# 4_MotorDrive.net
KiCad netlist of a schematic drawn in Altium Designer
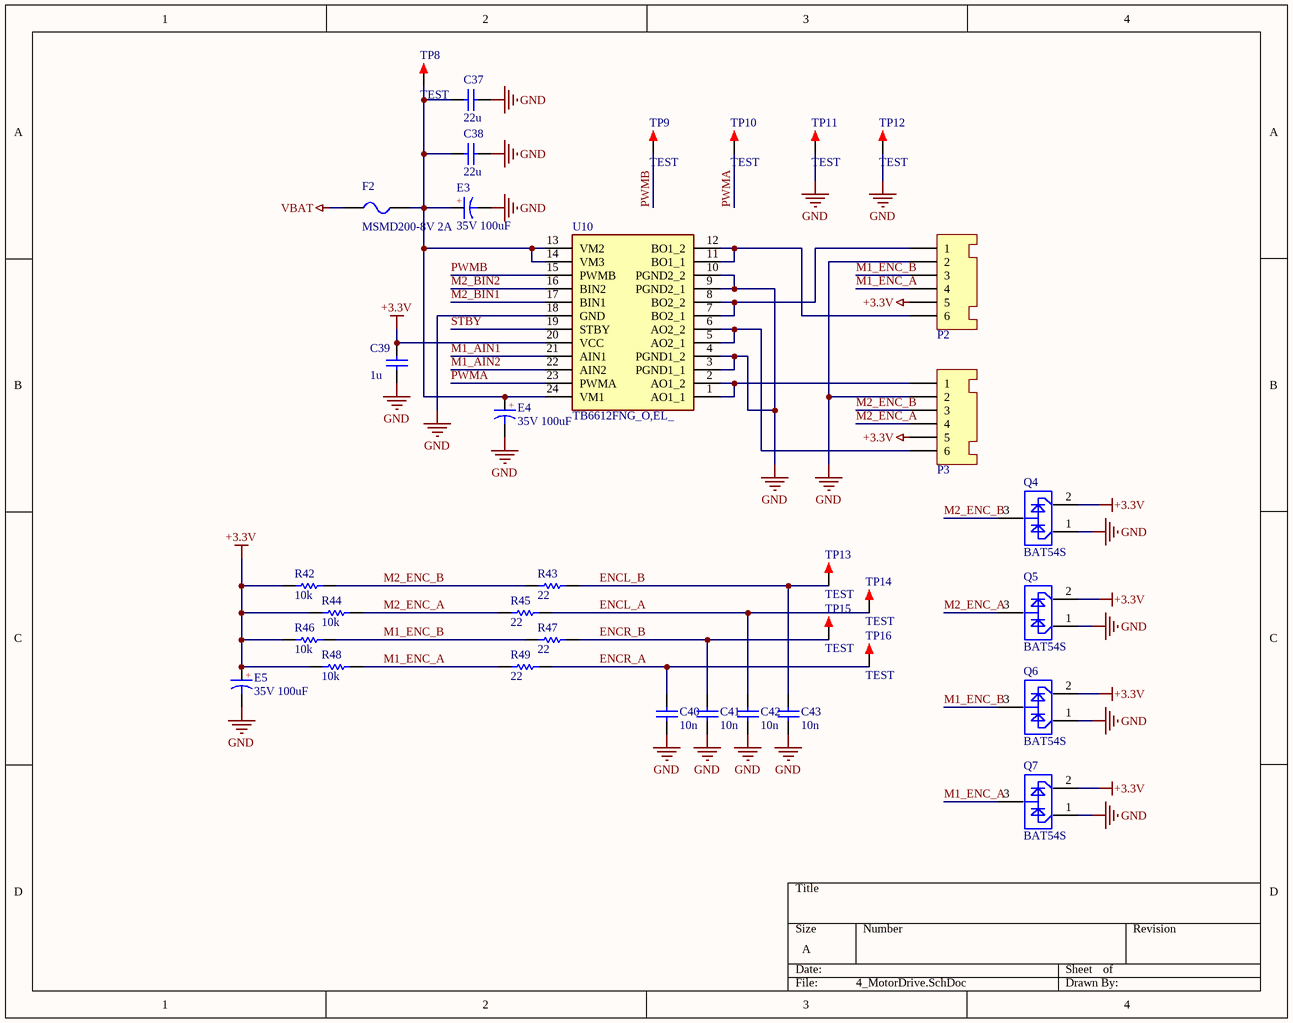
[diagram p0: 4_MotorDrive.SchDoc]

(export (version "E")
  (design (tool "Eeschema 10.0.6"))
  (components
    (comp (ref "C37")
      (value "22u")
      (footprint "C1812_L")
      (description "贴片电容")
      (libsource (lib "0.1 - 电阻-电容-电感-电位器") (part "C"))
    )
    (comp (ref "C38")
      (value "22u")
      (footprint "C1812_L")
      (description "贴片电容")
      (libsource (lib "0.1 - 电阻-电容-电感-电位器") (part "C"))
    )
    (comp (ref "C39")
      (value "1u")
      (footprint "CAP_0603_SMD")
      (description "Capacitor, 0603, SMD")
      (fields (field (name "PUBLISHER") "Altium Limited"))
      (libsource (lib "myRLC") (part "CAP_0603_SMD"))
    )
    (comp (ref "C40")
      (value "10n")
      (footprint "CAP_0603_SMD")
      (description "Capacitor, 0603, SMD")
      (fields (field (name "PUBLISHER") "Altium Limited"))
      (libsource (lib "myRLC") (part "CAP_0603_SMD"))
    )
    (comp (ref "C41")
      (value "10n")
      (footprint "CAP_0603_SMD")
      (description "Capacitor, 0603, SMD")
      (fields (field (name "PUBLISHER") "Altium Limited"))
      (libsource (lib "myRLC") (part "CAP_0603_SMD"))
    )
    (comp (ref "C42")
      (value "10n")
      (footprint "CAP_0603_SMD")
      (description "Capacitor, 0603, SMD")
      (fields (field (name "PUBLISHER") "Altium Limited"))
      (libsource (lib "myRLC") (part "CAP_0603_SMD"))
    )
    (comp (ref "C43")
      (value "10n")
      (footprint "CAP_0603_SMD")
      (description "Capacitor, 0603, SMD")
      (fields (field (name "PUBLISHER") "Altium Limited"))
      (libsource (lib "myRLC") (part "CAP_0603_SMD"))
    )
    (comp (ref "E3")
      (value "35V 100uF")
      (footprint "CE D(6.3*7.7)")
      (description "贴片电解电容")
      (libsource (lib "0.1 - 电阻-电容-电感-电位器") (part "CE_SMD"))
    )
    (comp (ref "E4")
      (value "35V 100uF")
      (footprint "CE D(6.3*7.7)")
      (description "贴片电解电容")
      (libsource (lib "0.1 - 电阻-电容-电感-电位器") (part "CE_SMD"))
    )
    (comp (ref "E5")
      (value "35V 100uF")
      (footprint "CE D(6.3*7.7)")
      (description "贴片电解电容")
      (libsource (lib "0.1 - 电阻-电容-电感-电位器") (part "CE_SMD"))
    )
    (comp (ref "F2")
      (value "MSMD200-8V 2A")
      (footprint "FU 1812")
      (description "贴片保险丝")
      (libsource (lib "0.5 - 保险丝-晶振-光耦") (part "FU"))
    )
    (comp (ref "P2")
      (value "HDR-1X6")
      (footprint "XH2.54-WS-6P")
      (description "6P接插件")
      (libsource (lib "5.4 - 接插件-脚距2.54 (100mil) ") (part "Header 6"))
    )
    (comp (ref "P3")
      (value "HDR-1X6")
      (footprint "XH2.54-WS-6P")
      (description "6P接插件")
      (libsource (lib "5.4 - 接插件-脚距2.54 (100mil) ") (part "Header 6"))
    )
    (comp (ref "Q4")
      (value "BAT54S")
      (footprint "TR_SOT-23")
      (description "Dual Schottky Diodes, SOT23")
      (libsource (lib "myTransistors&Diodes") (part "BAT54S"))
    )
    (comp (ref "Q5")
      (value "BAT54S")
      (footprint "TR_SOT-23")
      (description "Dual Schottky Diodes, SOT23")
      (libsource (lib "myTransistors&Diodes") (part "BAT54S"))
    )
    (comp (ref "Q6")
      (value "BAT54S")
      (footprint "TR_SOT-23")
      (description "Dual Schottky Diodes, SOT23")
      (libsource (lib "myTransistors&Diodes") (part "BAT54S"))
    )
    (comp (ref "Q7")
      (value "BAT54S")
      (footprint "TR_SOT-23")
      (description "Dual Schottky Diodes, SOT23")
      (libsource (lib "myTransistors&Diodes") (part "BAT54S"))
    )
    (comp (ref "R42")
      (value "10k")
      (footprint "RES_0603_SMD")
      (description "Resistor, 0603, SMD")
      (fields (field (name "PUBLISHER") "Altium Limited"))
      (libsource (lib "myRLC") (part "RES_0603_SMD"))
    )
    (comp (ref "R43")
      (value "22")
      (footprint "RES_0603_SMD")
      (description "Resistor, 0603, SMD")
      (fields (field (name "PUBLISHER") "Altium Limited"))
      (libsource (lib "myRLC") (part "RES_0603_SMD"))
    )
    (comp (ref "R44")
      (value "10k")
      (footprint "RES_0603_SMD")
      (description "Resistor, 0603, SMD")
      (fields (field (name "PUBLISHER") "Altium Limited"))
      (libsource (lib "myRLC") (part "RES_0603_SMD"))
    )
    (comp (ref "R45")
      (value "22")
      (footprint "RES_0603_SMD")
      (description "Resistor, 0603, SMD")
      (fields (field (name "PUBLISHER") "Altium Limited"))
      (libsource (lib "myRLC") (part "RES_0603_SMD"))
    )
    (comp (ref "R46")
      (value "10k")
      (footprint "RES_0603_SMD")
      (description "Resistor, 0603, SMD")
      (fields (field (name "PUBLISHER") "Altium Limited"))
      (libsource (lib "myRLC") (part "RES_0603_SMD"))
    )
    (comp (ref "R47")
      (value "22")
      (footprint "RES_0603_SMD")
      (description "Resistor, 0603, SMD")
      (fields (field (name "PUBLISHER") "Altium Limited"))
      (libsource (lib "myRLC") (part "RES_0603_SMD"))
    )
    (comp (ref "R48")
      (value "10k")
      (footprint "RES_0603_SMD")
      (description "Resistor, 0603, SMD")
      (fields (field (name "PUBLISHER") "Altium Limited"))
      (libsource (lib "myRLC") (part "RES_0603_SMD"))
    )
    (comp (ref "R49")
      (value "22")
      (footprint "RES_0603_SMD")
      (description "Resistor, 0603, SMD")
      (fields (field (name "PUBLISHER") "Altium Limited"))
      (libsource (lib "myRLC") (part "RES_0603_SMD"))
    )
    (comp (ref "TP8")
      (value "TEST")
      (footprint "TEST 1.2")
      (description "测试点")
      (libsource (lib "0.7 - 常用按键-开关-蜂鸣器-电池-测试点") (part "TEST"))
    )
    (comp (ref "TP9")
      (value "TEST")
      (footprint "TEST 1.2")
      (description "测试点")
      (libsource (lib "0.7 - 常用按键-开关-蜂鸣器-电池-测试点") (part "TEST"))
    )
    (comp (ref "TP10")
      (value "TEST")
      (footprint "TEST 1.2")
      (description "测试点")
      (libsource (lib "0.7 - 常用按键-开关-蜂鸣器-电池-测试点") (part "TEST"))
    )
    (comp (ref "TP11")
      (value "TEST")
      (footprint "TEST 1.2")
      (description "测试点")
      (libsource (lib "0.7 - 常用按键-开关-蜂鸣器-电池-测试点") (part "TEST"))
    )
    (comp (ref "TP12")
      (value "TEST")
      (footprint "TEST 1.2")
      (description "测试点")
      (libsource (lib "0.7 - 常用按键-开关-蜂鸣器-电池-测试点") (part "TEST"))
    )
    (comp (ref "TP13")
      (value "TEST")
      (footprint "TEST 1.2")
      (description "测试点")
      (libsource (lib "0.7 - 常用按键-开关-蜂鸣器-电池-测试点") (part "TEST"))
    )
    (comp (ref "TP14")
      (value "TEST")
      (footprint "TEST 1.2")
      (description "测试点")
      (libsource (lib "0.7 - 常用按键-开关-蜂鸣器-电池-测试点") (part "TEST"))
    )
    (comp (ref "TP15")
      (value "TEST")
      (footprint "TEST 1.2")
      (description "测试点")
      (libsource (lib "0.7 - 常用按键-开关-蜂鸣器-电池-测试点") (part "TEST"))
    )
    (comp (ref "TP16")
      (value "TEST")
      (footprint "TEST 1.2")
      (description "测试点")
      (libsource (lib "0.7 - 常用按键-开关-蜂鸣器-电池-测试点") (part "TEST"))
    )
    (comp (ref "U10")
      (value "TB6612FNG_O,EL_")
      (footprint "TKY:SOP65P760X160-24N")
      (description "Integrated Circuit")
      (fields
        (field (name "MANUFACTURER_PART_NUMBER") "TB6612FNG(O,EL)")
        (field (name "MOUSER PART NUMBER") "757-TB6612FNG(O,EL)")
      )
      (libsource (lib "*") (part "TB6612FNG_O,EL_"))
    )
  )
  (nets
    (net (code "1") (name "+3.3V") (class "Default")
      (node (ref "C39") (pin "1") (pinfunction "1_1") (pintype "passive"))
      (node (ref "E5") (pin "1") (pinfunction "1_1") (pintype "passive"))
      (node (ref "P2") (pin "5") (pinfunction "5_5") (pintype "passive"))
      (node (ref "P3") (pin "5") (pinfunction "5_5") (pintype "passive"))
      (node (ref "Q4") (pin "2") (pinfunction "2_2") (pintype "passive"))
      (node (ref "Q5") (pin "2") (pinfunction "2_2") (pintype "passive"))
      (node (ref "Q6") (pin "2") (pinfunction "2_2") (pintype "passive"))
      (node (ref "Q7") (pin "2") (pinfunction "2_2") (pintype "passive"))
      (node (ref "R42") (pin "2") (pinfunction "2_2") (pintype "passive"))
      (node (ref "R44") (pin "2") (pinfunction "2_2") (pintype "passive"))
      (node (ref "R46") (pin "2") (pinfunction "2_2") (pintype "passive"))
      (node (ref "R48") (pin "2") (pinfunction "2_2") (pintype "passive"))
      (node (ref "U10") (pin "20") (pinfunction "VCC_20") (pintype "passive"))
    )
    (net (code "2") (name "/ENCL_A") (class "Default")
      (node (ref "C42") (pin "1") (pinfunction "1_1") (pintype "passive"))
      (node (ref "R45") (pin "1") (pinfunction "1_1") (pintype "passive"))
      (node (ref "TP14") (pin "1") (pinfunction "1_1") (pintype "passive"))
    )
    (net (code "3") (name "/ENCL_B") (class "Default")
      (node (ref "C43") (pin "1") (pinfunction "1_1") (pintype "passive"))
      (node (ref "R43") (pin "1") (pinfunction "1_1") (pintype "passive"))
      (node (ref "TP13") (pin "1") (pinfunction "1_1") (pintype "passive"))
    )
    (net (code "4") (name "/ENCR_A") (class "Default")
      (node (ref "C40") (pin "1") (pinfunction "1_1") (pintype "passive"))
      (node (ref "R49") (pin "1") (pinfunction "1_1") (pintype "passive"))
      (node (ref "TP16") (pin "1") (pinfunction "1_1") (pintype "passive"))
    )
    (net (code "5") (name "/ENCR_B") (class "Default")
      (node (ref "C41") (pin "1") (pinfunction "1_1") (pintype "passive"))
      (node (ref "R47") (pin "1") (pinfunction "1_1") (pintype "passive"))
      (node (ref "TP15") (pin "1") (pinfunction "1_1") (pintype "passive"))
    )
    (net (code "6") (name "/M1_AIN1") (class "Default")
      (node (ref "U10") (pin "21") (pinfunction "AIN1_21") (pintype "passive"))
    )
    (net (code "7") (name "/M1_AIN2") (class "Default")
      (node (ref "U10") (pin "22") (pinfunction "AIN2_22") (pintype "passive"))
    )
    (net (code "8") (name "/M1_ENC_A") (class "Default")
      (node (ref "P2") (pin "4") (pinfunction "4_4") (pintype "passive"))
      (node (ref "Q7") (pin "3") (pinfunction "3_3") (pintype "passive"))
      (node (ref "R48") (pin "1") (pinfunction "1_1") (pintype "passive"))
      (node (ref "R49") (pin "2") (pinfunction "2_2") (pintype "passive"))
    )
    (net (code "9") (name "/M1_ENC_B") (class "Default")
      (node (ref "P2") (pin "3") (pinfunction "3_3") (pintype "passive"))
      (node (ref "Q6") (pin "3") (pinfunction "3_3") (pintype "passive"))
      (node (ref "R46") (pin "1") (pinfunction "1_1") (pintype "passive"))
      (node (ref "R47") (pin "2") (pinfunction "2_2") (pintype "passive"))
    )
    (net (code "10") (name "/M2_BIN1") (class "Default")
      (node (ref "U10") (pin "17") (pinfunction "BIN1_17") (pintype "passive"))
    )
    (net (code "11") (name "/M2_BIN2") (class "Default")
      (node (ref "U10") (pin "16") (pinfunction "BIN2_16") (pintype "passive"))
    )
    (net (code "12") (name "/M2_ENC_A") (class "Default")
      (node (ref "P3") (pin "4") (pinfunction "4_4") (pintype "passive"))
      (node (ref "Q5") (pin "3") (pinfunction "3_3") (pintype "passive"))
      (node (ref "R44") (pin "1") (pinfunction "1_1") (pintype "passive"))
      (node (ref "R45") (pin "2") (pinfunction "2_2") (pintype "passive"))
    )
    (net (code "13") (name "/M2_ENC_B") (class "Default")
      (node (ref "P3") (pin "3") (pinfunction "3_3") (pintype "passive"))
      (node (ref "Q4") (pin "3") (pinfunction "3_3") (pintype "passive"))
      (node (ref "R42") (pin "1") (pinfunction "1_1") (pintype "passive"))
      (node (ref "R43") (pin "2") (pinfunction "2_2") (pintype "passive"))
    )
    (net (code "14") (name "/PWMA") (class "Default")
      (node (ref "TP10") (pin "1") (pinfunction "1_1") (pintype "passive"))
      (node (ref "U10") (pin "23") (pinfunction "PWMA_23") (pintype "passive"))
    )
    (net (code "15") (name "/PWMB") (class "Default")
      (node (ref "TP9") (pin "1") (pinfunction "1_1") (pintype "passive"))
      (node (ref "U10") (pin "15") (pinfunction "PWMB_15") (pintype "passive"))
    )
    (net (code "16") (name "/STBY") (class "Default")
      (node (ref "U10") (pin "19") (pinfunction "STBY_19") (pintype "passive"))
    )
    (net (code "17") (name "GND") (class "Default")
      (node (ref "C37") (pin "1") (pinfunction "1_1") (pintype "passive"))
      (node (ref "C38") (pin "1") (pinfunction "1_1") (pintype "passive"))
      (node (ref "C39") (pin "2") (pinfunction "2_2") (pintype "passive"))
      (node (ref "C40") (pin "2") (pinfunction "2_2") (pintype "passive"))
      (node (ref "C41") (pin "2") (pinfunction "2_2") (pintype "passive"))
      (node (ref "C42") (pin "2") (pinfunction "2_2") (pintype "passive"))
      (node (ref "C43") (pin "2") (pinfunction "2_2") (pintype "passive"))
      (node (ref "E3") (pin "2") (pinfunction "2_2") (pintype "passive"))
      (node (ref "E4") (pin "2") (pinfunction "2_2") (pintype "passive"))
      (node (ref "E5") (pin "2") (pinfunction "2_2") (pintype "passive"))
      (node (ref "P2") (pin "2") (pinfunction "2_2") (pintype "passive"))
      (node (ref "P3") (pin "2") (pinfunction "2_2") (pintype "passive"))
      (node (ref "Q4") (pin "1") (pinfunction "1_1") (pintype "passive"))
      (node (ref "Q5") (pin "1") (pinfunction "1_1") (pintype "passive"))
      (node (ref "Q6") (pin "1") (pinfunction "1_1") (pintype "passive"))
      (node (ref "Q7") (pin "1") (pinfunction "1_1") (pintype "passive"))
      (node (ref "TP11") (pin "1") (pinfunction "1_1") (pintype "passive"))
      (node (ref "TP12") (pin "1") (pinfunction "1_1") (pintype "passive"))
      (node (ref "U10") (pin "10") (pinfunction "PGND2_2_10") (pintype "passive"))
      (node (ref "U10") (pin "18") (pinfunction "GND_18") (pintype "passive"))
      (node (ref "U10") (pin "3") (pinfunction "PGND1_1_3") (pintype "passive"))
      (node (ref "U10") (pin "4") (pinfunction "PGND1_2_4") (pintype "passive"))
      (node (ref "U10") (pin "9") (pinfunction "PGND2_1_9") (pintype "passive"))
    )
    (net (code "18") (name "Net-(U10-AO1_1)") (class "Default")
      (node (ref "P3") (pin "1") (pinfunction "1_1") (pintype "passive"))
      (node (ref "U10") (pin "1") (pinfunction "AO1_1_1") (pintype "passive"))
      (node (ref "U10") (pin "2") (pinfunction "AO1_2_2") (pintype "passive"))
    )
    (net (code "19") (name "Net-(U10-AO2_1)") (class "Default")
      (node (ref "P3") (pin "6") (pinfunction "6_6") (pintype "passive"))
      (node (ref "U10") (pin "5") (pinfunction "AO2_1_5") (pintype "passive"))
      (node (ref "U10") (pin "6") (pinfunction "AO2_2_6") (pintype "passive"))
    )
    (net (code "20") (name "Net-(U10-BO1_1)") (class "Default")
      (node (ref "P2") (pin "6") (pinfunction "6_6") (pintype "passive"))
      (node (ref "U10") (pin "11") (pinfunction "BO1_1_11") (pintype "passive"))
      (node (ref "U10") (pin "12") (pinfunction "BO1_2_12") (pintype "passive"))
    )
    (net (code "21") (name "Net-(U10-BO2_1)") (class "Default")
      (node (ref "P2") (pin "1") (pinfunction "1_1") (pintype "passive"))
      (node (ref "U10") (pin "7") (pinfunction "BO2_1_7") (pintype "passive"))
      (node (ref "U10") (pin "8") (pinfunction "BO2_2_8") (pintype "passive"))
    )
    (net (code "22") (name "Net-(U10-VM1)") (class "Default")
      (node (ref "C37") (pin "2") (pinfunction "2_2") (pintype "passive"))
      (node (ref "C38") (pin "2") (pinfunction "2_2") (pintype "passive"))
      (node (ref "E3") (pin "1") (pinfunction "1_1") (pintype "passive"))
      (node (ref "E4") (pin "1") (pinfunction "1_1") (pintype "passive"))
      (node (ref "F2") (pin "2") (pinfunction "2_2") (pintype "passive"))
      (node (ref "TP8") (pin "1") (pinfunction "1_1") (pintype "passive"))
      (node (ref "U10") (pin "13") (pinfunction "VM2_13") (pintype "passive"))
      (node (ref "U10") (pin "14") (pinfunction "VM3_14") (pintype "passive"))
      (node (ref "U10") (pin "24") (pinfunction "VM1_24") (pintype "passive"))
    )
    (net (code "23") (name "VBAT") (class "Default")
      (node (ref "F2") (pin "1") (pinfunction "1_1") (pintype "passive"))
    )
  )
)
